# Transistor_Driver.net
KiCad netlist of a schematic drawn in Altium Designer
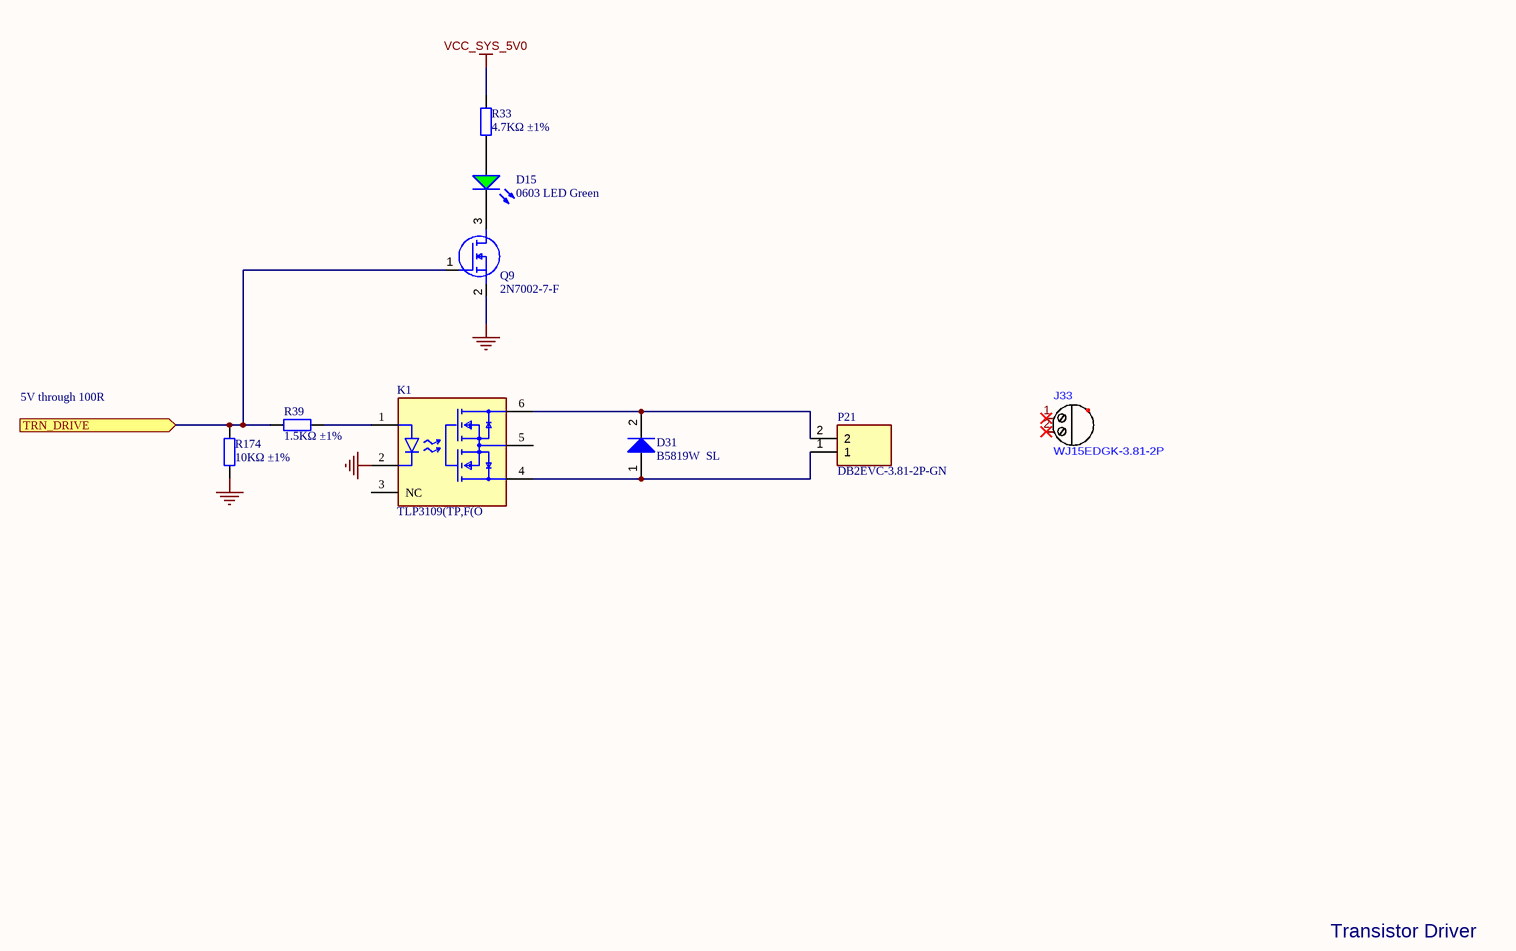
[diagram p0: Transistor_Driver.SchDoc]

(export (version "E")
  (design (tool "Eeschema 10.0.6"))
  (components
    (comp (ref "D15")
      (value "0603 LED Green")
      (footprint "0603_LED_S1 - GREEN")
      (fields
        (field (name "MANUFACTURER PART NUMBER") "19-217/GHC-YR1S2/3T")
        (field (name "MANUFACTURER") "Everlight Elec")
      )
      (libsource (lib "Sienci_Labs") (part "19-217/GHC-YR1S2/3T"))
    )
    (comp (ref "D31")
      (value "B5819W  SL")
      (footprint "SOD-123")
      (description "Schottky Diode")
      (fields
        (field (name "MANUFACTURER PART NUMBER") "B5819W SL")
        (field (name "MANUFACTURER") "Jiangsu Changjing Electronics Technology")
      )
      (libsource (lib "Diode") (part "SOD-123 B5819W  SL"))
    )
    (comp (ref "J33")
      (value "WJ15EDGK-3.81-2P")
      (description "2 1 3.81mm Green Plug P=3.81mm Pluggable System Terminal Block ROHS")
      (fields (field (name "MANUFACTURER") "Ningbo"))
      (libsource (lib "Sienci_Labs") (part "WJ15EDGK-3.81-2P"))
    )
    (comp (ref "K1")
      (value "TLP3109(TP,F(O")
      (footprint "FP-11-7C1S-MFG")
      (description "Form A(SPST-NO) 1.33V 100V 45mΩ 2A DC SMD-6P Solid State Relays - MOS Output (PhotoMOS) ROHS")
      (fields (field (name "MANUFACTURER") "Toshiba"))
      (libsource (lib "Sienci_Labs") (part "TLP3109(TP,F(O"))
    )
    (comp (ref "P21")
      (value "DB2EVC-3.81-2P-GN")
      (footprint "CONN-TH_5P-P3.81_DB2EVC-3.81-2p")
      (description "3.81mm Green Board Edge/Receptacle-Close Push-Pull,P=3.81mm Pluggable System Terminal Block ROHS")
      (fields (field (name "MANUFACTURER") "DIBO"))
      (libsource (lib "Sienci_Labs") (part "DB2EVC-3.81-2P-GN"))
    )
    (comp (ref "Q9")
      (value "2N7002-7-F")
      (footprint "SOT-23(SOT-23-3)")
      (description "60V 115mA 7.5Ω@5V,50mA 370mW N Channel SOT-23 MOSFETs ROHS")
      (fields (field (name "MANUFACTURER") "Diodes Inc.") (field (name "MOUSER PART NUMBER") "621-2N7002-F"))
      (libsource (lib "Sienci_Labs") (part "2N7002-7-F"))
    )
    (comp (ref "R33")
      (value "4.7KΩ ±1%")
      (footprint "0402_R")
      (description "Chip resistor")
      (fields
        (field (name "MANUFACTURER") "Uniroyal Elec")
        (field (name "MANUFACTURER PART NUMBER") "0402WGF4701TCE")
      )
      (libsource (lib "RES") (part "0402 4.7K (4701) 1%"))
    )
    (comp (ref "R39")
      (value "1.5KΩ ±1%")
      (footprint "0402_R")
      (description "Chip resistor")
      (fields
        (field (name "MANUFACTURER") "Uniroyal Elec")
        (field (name "MANUFACTURER PART NUMBER") "0402WGF1501TCE")
      )
      (libsource (lib "RES") (part "0402 1.5K (1501) 1%"))
    )
    (comp (ref "R174")
      (value "10KΩ ±1%")
      (footprint "0402_R")
      (description "Chip resistor")
      (fields
        (field (name "MANUFACTURER") "Uniroyal Elec")
        (field (name "MANUFACTURER PART NUMBER") "0402WGF1002TCE")
      )
      (libsource (lib "RES") (part "0402 10K (1002) 1%"))
    )
  )
  (nets
    (net (code "1") (name "/TRN_DRIVE") (class "Default")
      (node (ref "Q9") (pin "1") (pinfunction "G_1") (pintype "passive"))
      (node (ref "R174") (pin "2") (pinfunction "2_2") (pintype "passive"))
      (node (ref "R39") (pin "1") (pinfunction "1_1") (pintype "passive"))
    )
    (net (code "2") (name "GND") (class "Default")
      (node (ref "K1") (pin "2") (pinfunction "C_2") (pintype "passive"))
      (node (ref "Q9") (pin "2") (pinfunction "S_2") (pintype "passive"))
      (node (ref "R174") (pin "1") (pinfunction "1_1") (pintype "passive"))
    )
    (net (code "3") (name "Net-(D15-PadA)") (class "Default")
      (node (ref "D15") (pin "A") (pinfunction "A_A") (pintype "passive"))
      (node (ref "R33") (pin "1") (pinfunction "1_1") (pintype "passive"))
    )
    (net (code "4") (name "Net-(D31-A)") (class "Default")
      (node (ref "D31") (pin "1") (pinfunction "A_1") (pintype "passive"))
      (node (ref "K1") (pin "4") (pinfunction "Drain_4") (pintype "passive"))
      (node (ref "P21") (pin "1") (pinfunction "1_1") (pintype "passive"))
    )
    (net (code "5") (name "Net-(D31-K)") (class "Default")
      (node (ref "D31") (pin "2") (pinfunction "K_2") (pintype "passive"))
      (node (ref "K1") (pin "6") (pinfunction "Drain_6") (pintype "passive"))
      (node (ref "P21") (pin "2") (pinfunction "2_2") (pintype "passive"))
    )
    (net (code "6") (name "Net-(K1-A)") (class "Default")
      (node (ref "K1") (pin "1") (pinfunction "A_1") (pintype "passive"))
      (node (ref "R39") (pin "2") (pinfunction "2_2") (pintype "passive"))
    )
    (net (code "7") (name "Net-(Q9-D)") (class "Default")
      (node (ref "D15") (pin "K") (pinfunction "K_K") (pintype "passive"))
      (node (ref "Q9") (pin "3") (pinfunction "D_3") (pintype "passive"))
    )
    (net (code "8") (name "VCC_SYS_5V0") (class "Default")
      (node (ref "R33") (pin "2") (pinfunction "2_2") (pintype "passive"))
    )
    (net (code "9") (name "unconnected-(J33-Pad1)") (class "Default")
      (node (ref "J33") (pin "1") (pinfunction "1_1") (pintype "passive+no_connect"))
    )
    (net (code "10") (name "unconnected-(J33-Pad2)") (class "Default")
      (node (ref "J33") (pin "2") (pinfunction "2_2") (pintype "passive+no_connect"))
    )
    (net (code "11") (name "unconnected-(K1-NC-Pad3)") (class "Default")
      (node (ref "K1") (pin "3") (pinfunction "NC_3") (pintype "passive"))
    )
    (net (code "12") (name "unconnected-(K1-Source-Pad5)") (class "Default")
      (node (ref "K1") (pin "5") (pinfunction "Source_5") (pintype "passive"))
    )
  )
)
